# SensePlates.net
KiCad netlist of a schematic drawn in Altium Designer
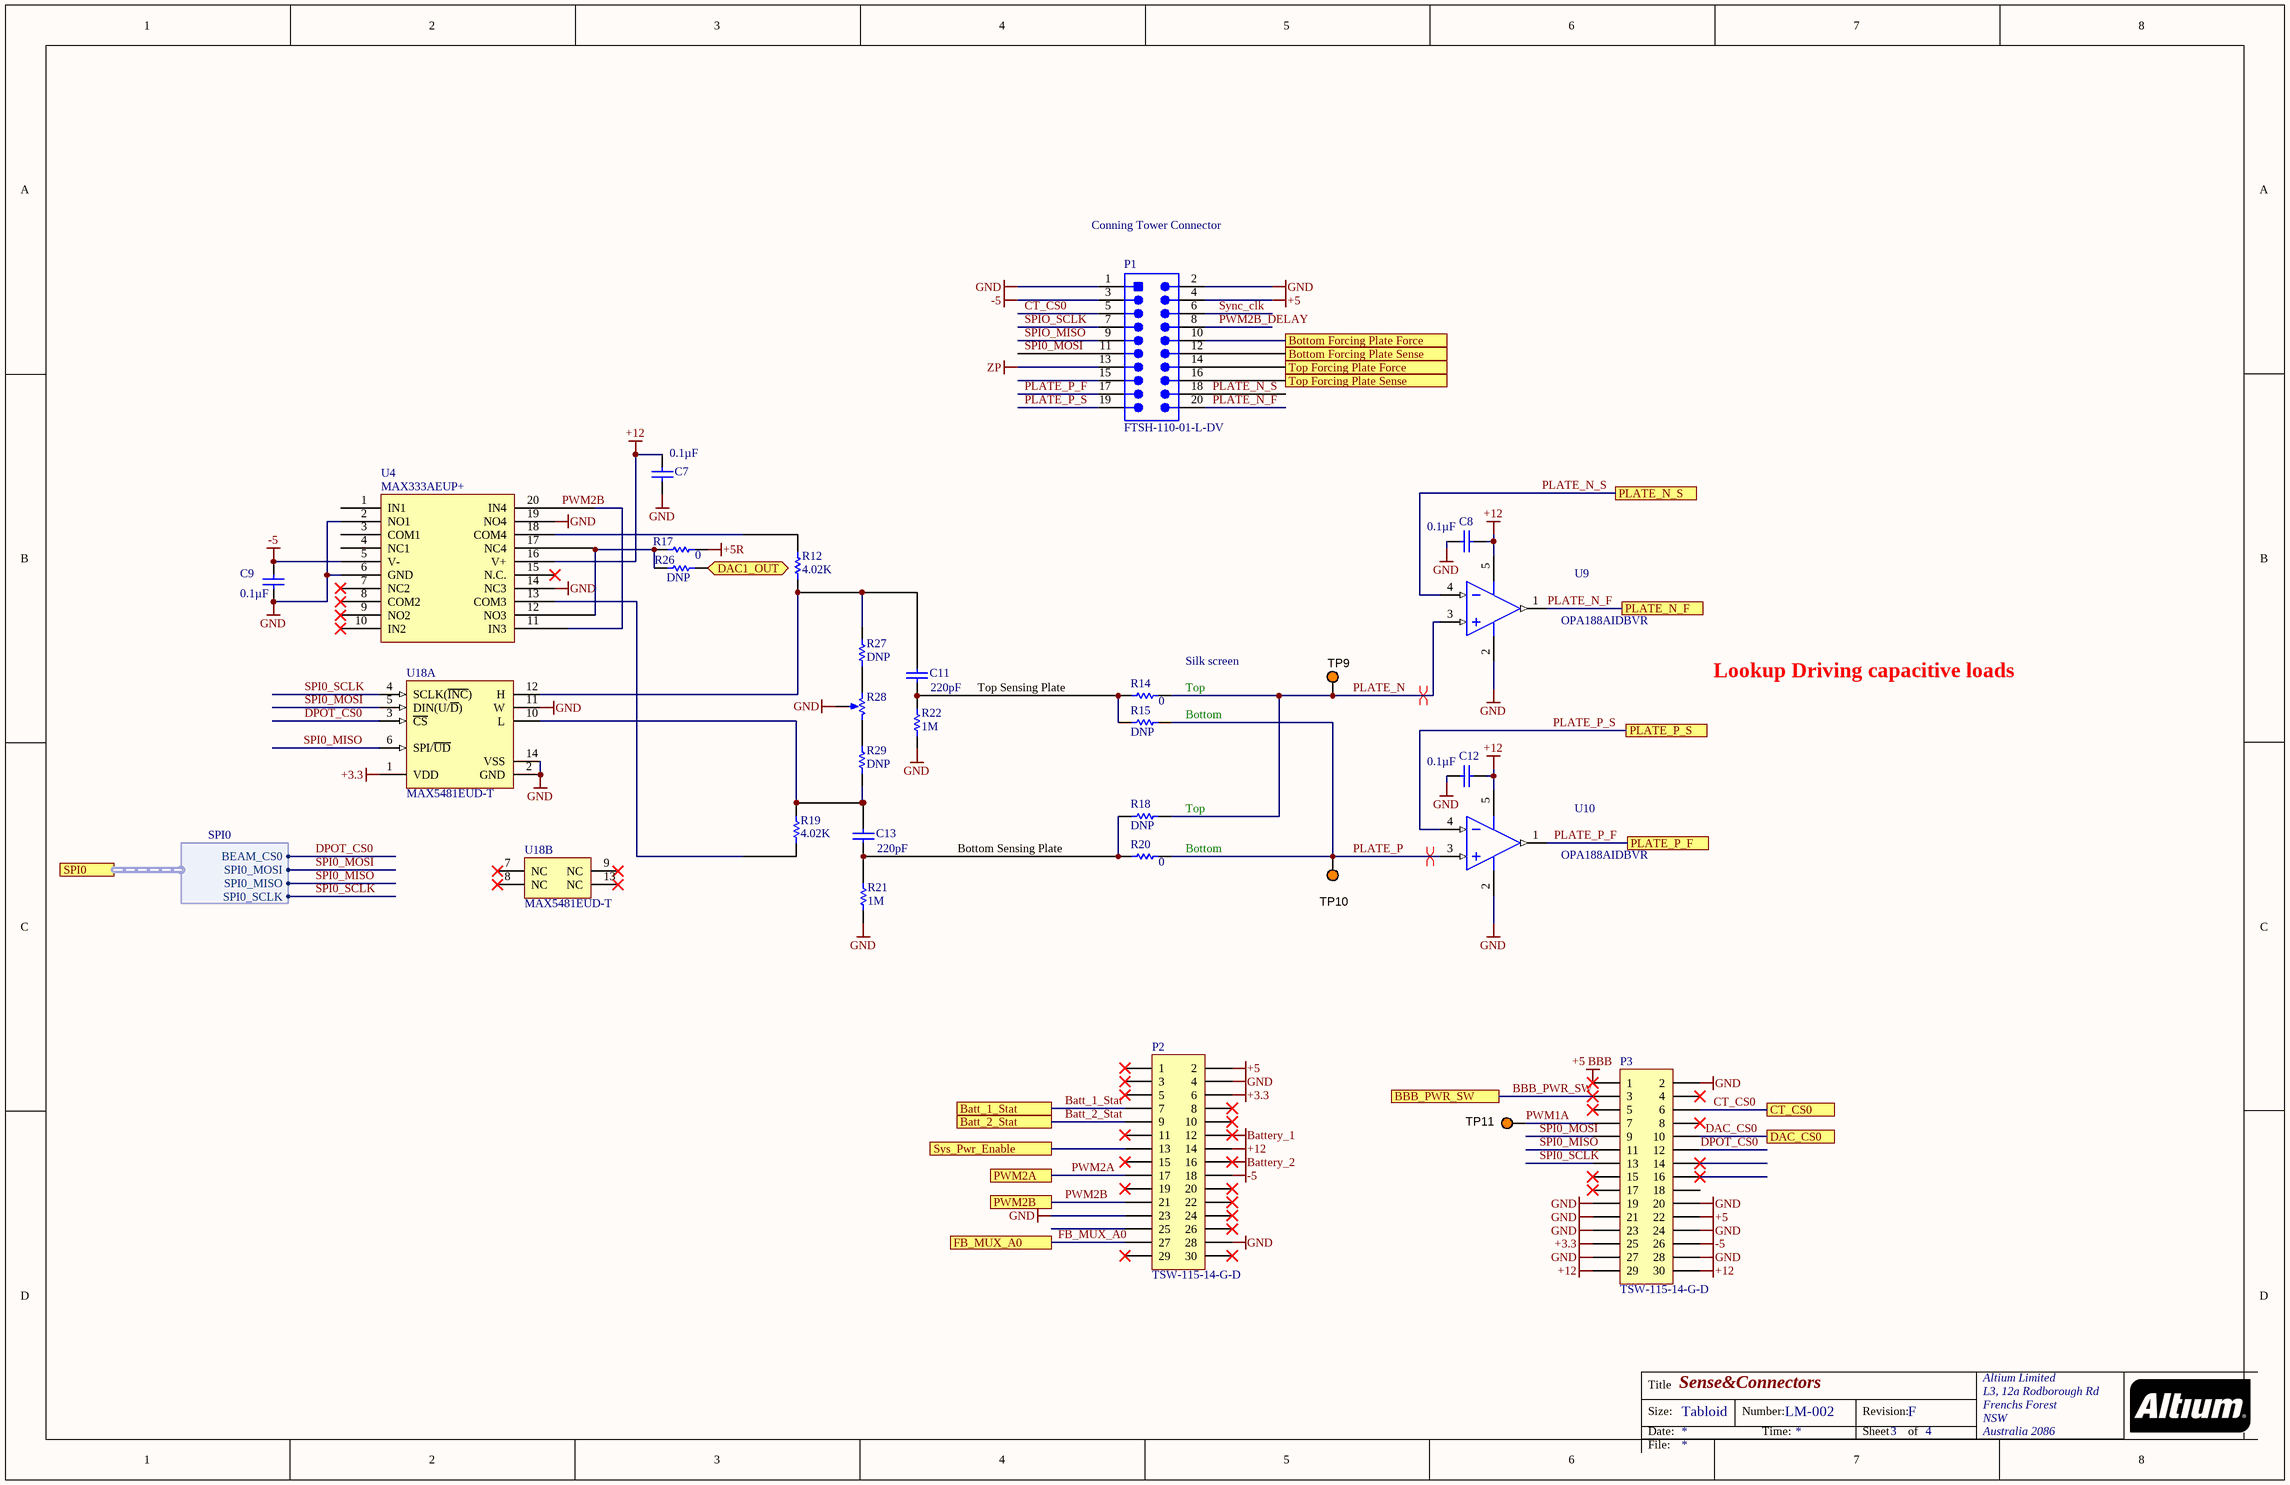
[diagram p0: SensePlates.SchDoc]

(export (version "E")
  (design (tool "Eeschema 10.0.6"))
  (components
    (comp (ref "C7")
      (value "CAP CER 0.1UF 25V X7R 0805")
      (footprint "CAPC0805(2012)145_N")
      (fields
        (field (name "MANUFACTURER") "Murata Electronics North America")
        (field (name "MANUFACTURER PART NUMBER") "GRM21BR71E104KA01L")
        (field (name "CAPACITANCE") "0.1µF")
        (field (name "TOLERANCE") "±10%")
      )
      (libsource (lib "Altium Content Vault") (part "CMP-1036-04795-1"))
    )
    (comp (ref "C8")
      (value "CAP CER 0.1UF 25V X7R 0805")
      (footprint "CAPC0805(2012)145_N")
      (fields
        (field (name "MANUFACTURER") "Murata Electronics North America")
        (field (name "MANUFACTURER PART NUMBER") "GRM21BR71E104KA01L")
        (field (name "CAPACITANCE") "0.1µF")
        (field (name "TOLERANCE") "±10%")
      )
      (libsource (lib "Altium Content Vault") (part "CMP-1036-04795-1"))
    )
    (comp (ref "C9")
      (value "CAP CER 0.1UF 25V X7R 0805")
      (footprint "CAPC0805(2012)145_N")
      (fields
        (field (name "MANUFACTURER") "Murata Electronics North America")
        (field (name "MANUFACTURER PART NUMBER") "GRM21BR71E104KA01L")
        (field (name "CAPACITANCE") "0.1µF")
        (field (name "TOLERANCE") "±10%")
      )
      (libsource (lib "Altium Content Vault") (part "CMP-1036-04795-1"))
    )
    (comp (ref "C11")
      (value "CAP CER 1UF 25V X7R 0805")
      (footprint "CAPC0805(2012)155_L")
      (fields
        (field (name "MANUFACTURER") "Murata Electronics North America")
        (field (name "MANUFACTURER PART NUMBER") "GRM21BR71E105KA99L")
        (field (name "CAPACITANCE") "220pF")
        (field (name "TOLERANCE") "±10%")
      )
      (libsource (lib "Altium Content Vault") (part "CMP-1036-04882-1"))
    )
    (comp (ref "C12")
      (value "CAP CER 0.1UF 25V X7R 0805")
      (footprint "CAPC0805(2012)145_N")
      (fields
        (field (name "MANUFACTURER") "Murata Electronics North America")
        (field (name "MANUFACTURER PART NUMBER") "GRM21BR71E104KA01L")
        (field (name "CAPACITANCE") "0.1µF")
        (field (name "TOLERANCE") "±10%")
      )
      (libsource (lib "Altium Content Vault") (part "CMP-1036-04795-1"))
    )
    (comp (ref "C13")
      (value "CAP CER 1UF 25V X7R 0805")
      (footprint "CAPC0805(2012)155_L")
      (fields
        (field (name "MANUFACTURER") "Murata Electronics North America")
        (field (name "MANUFACTURER PART NUMBER") "GRM21BR71E105KA99L")
        (field (name "CAPACITANCE") "220pF")
        (field (name "TOLERANCE") "±10%")
      )
      (libsource (lib "Altium Content Vault") (part "CMP-1036-04882-1"))
    )
    (comp (ref "P1")
      (value "FTSH-110-01-L-DV")
      (footprint "SMTC-FTSH-110-01-L-DV_V")
      (description "Male Header, Pitch 1.27 mm, 2 x 10 Position, Height 6.1 mm, -55 to 125 degC, RoHS, Tube")
      (fields (field (name "MANUFACTURER") "Samtec"))
      (libsource (lib "Altium Content Vault") (part "CN-2P-M-R20_V1"))
    )
    (comp (ref "P2")
      (value "TSW-115-14-G-D")
      (footprint "TSW-115-14-G-D")
      (description "Header, 15-Pin, Dual row")
      (fields (field (name "MANUFACTURER") "Samtec Inc."))
      (libsource (lib "Miscellaneous Connectors") (part "Header 15X2"))
    )
    (comp (ref "P3")
      (value "TSW-115-14-G-D")
      (footprint "TSW-115-14-G-D")
      (description "Header, 15-Pin, Dual row")
      (fields (field (name "MANUFACTURER") "Samtec Inc."))
      (libsource (lib "Miscellaneous Connectors") (part "Header 15X2"))
    )
    (comp (ref "R12")
      (value "4.02K")
      (footprint "RESC0805(2012)_L")
      (description "RES SMD 4.02K OHM 1% 1/8W 0805")
      (fields
        (field (name "MANUFACTURER") "Vishay Dale")
        (field (name "MANUFACTURER PART NUMBER") "CRCW08054K02FKEAHP")
      )
      (libsource (lib "Altium Content Vault") (part "CMP-1013-00215-1"))
    )
    (comp (ref "R14")
      (value "0")
      (footprint "RESC0805(2012)_L")
      (description "RES SMD 0 OHM JUMPER 1/8W 0805")
      (fields
        (field (name "MANUFACTURER") "Panasonic Electronic Components")
        (field (name "MANUFACTURER PART NUMBER") "ERJ-6GEY0R00V")
      )
      (libsource (lib "Altium Content Vault") (part "CMP-1013-00215-1"))
    )
    (comp (ref "R15")
      (value "DNP")
      (footprint "RESC0805(2012)_L")
      (description "RES SMD 0 OHM JUMPER 1/8W 0805")
      (fields
        (field (name "MANUFACTURER") "Panasonic Electronic Components")
        (field (name "MANUFACTURER PART NUMBER") "ERJ-6GEY0R00V")
      )
      (libsource (lib "Altium Content Vault") (part "CMP-1013-00215-1"))
    )
    (comp (ref "R17")
      (value "0")
      (footprint "RESC0805(2012)_L")
      (description "RES SMD 0 OHM JUMPER 1/8W 0805")
      (fields
        (field (name "MANUFACTURER") "Panasonic Electronic Components")
        (field (name "MANUFACTURER PART NUMBER") "ERJ-6GEY0R00V")
      )
      (libsource (lib "Altium Content Vault") (part "CMP-1013-00215-1"))
    )
    (comp (ref "R18")
      (value "DNP")
      (footprint "RESC0805(2012)_L")
      (description "RES SMD 0 OHM JUMPER 1/8W 0805")
      (fields
        (field (name "MANUFACTURER") "Panasonic Electronic Components")
        (field (name "MANUFACTURER PART NUMBER") "ERJ-6GEY0R00V")
      )
      (libsource (lib "Altium Content Vault") (part "CMP-1013-00215-1"))
    )
    (comp (ref "R19")
      (value "4.02K")
      (footprint "RESC0805(2012)_L")
      (description "RES SMD 4.02K OHM 1% 1/8W 0805")
      (fields
        (field (name "MANUFACTURER") "Vishay Dale")
        (field (name "MANUFACTURER PART NUMBER") "CRCW08054K02FKEAHP")
      )
      (libsource (lib "Altium Content Vault") (part "CMP-1013-00215-1"))
    )
    (comp (ref "R20")
      (value "0")
      (footprint "RESC0805(2012)_L")
      (description "RES SMD 0 OHM JUMPER 1/8W 0805")
      (fields
        (field (name "MANUFACTURER") "Panasonic Electronic Components")
        (field (name "MANUFACTURER PART NUMBER") "ERJ-6GEY0R00V")
      )
      (libsource (lib "Altium Content Vault") (part "CMP-1013-00215-1"))
    )
    (comp (ref "R21")
      (value "1M")
      (footprint "RESC0805(2012)_L")
      (description "RES SMD 1M OHM 1% 1/8W 0805")
      (fields
        (field (name "MANUFACTURER") "Vishay Dale")
        (field (name "MANUFACTURER PART NUMBER") "RCV08051M00FKEA")
      )
      (libsource (lib "Altium Content Vault") (part "CMP-1013-00215-1"))
    )
    (comp (ref "R22")
      (value "1M")
      (footprint "RESC0805(2012)_L")
      (description "RES SMD 1M OHM 1% 1/8W 0805")
      (fields
        (field (name "MANUFACTURER") "Vishay Dale")
        (field (name "MANUFACTURER PART NUMBER") "RCV08051M00FKEA")
      )
      (libsource (lib "Altium Content Vault") (part "CMP-1013-00215-1"))
    )
    (comp (ref "R26")
      (value "DNP")
      (footprint "RESC0805(2012)_L")
      (description "RES SMD 0 OHM JUMPER 1/8W 0805")
      (fields
        (field (name "MANUFACTURER") "Panasonic Electronic Components")
        (field (name "MANUFACTURER PART NUMBER") "ERJ-6GEY0R00V")
      )
      (libsource (lib "Altium Content Vault") (part "CMP-1013-00215-1"))
    )
    (comp (ref "R27")
      (value "DNP")
      (footprint "RESC0402(1005)_M")
      (description "7.5K")
      (libsource (lib "Altium Content Vault") (part "CMP-1011-00463-1"))
    )
    (comp (ref "R28")
      (value "DNP")
      (footprint "Trimmer 2.54")
      (description "TRIMMER 5K OHM 0.25W PC PIN")
      (fields
        (field (name "MANUFACTURER") "Vishay Foil Resistors (Division of Vishay Precision Group)")
        (field (name "MANUFACTURER PART NUMBER") "Y00535K00000J0L")
      )
      (libsource (lib "ZLS_Schematic_lib") (part "Trimmer"))
    )
    (comp (ref "R29")
      (value "DNP")
      (footprint "RESC0402(1005)_M")
      (description "7.5K")
      (libsource (lib "Altium Content Vault") (part "CMP-1011-00463-1"))
    )
    (comp (ref "TP9")
      (value "5003")
      (footprint "KSTN-5003")
      (description "Test Point, Orange, 1-Pin THD, RoHS")
      (libsource (lib "Altium Content Vault") (part "CMP-1672-00009-1"))
    )
    (comp (ref "TP10")
      (value "5003")
      (footprint "KSTN-5003")
      (description "Test Point, Orange, 1-Pin THD, RoHS")
      (libsource (lib "Altium Content Vault") (part "CMP-1672-00009-1"))
    )
    (comp (ref "TP11")
      (value "5003")
      (footprint "KSTN-5003")
      (description "Test Point, Orange, 1-Pin THD, RoHS")
      (libsource (lib "Altium Content Vault") (part "CMP-1672-00009-1"))
    )
    (comp (ref "U4")
      (value "MAX333AEUP+")
      (footprint "TSOP65P640X90-20N")
      (description "IC SWITCH QUAD SPDT 20TSSOP")
      (fields (field (name "MANUFACTURER") "Maxim Integrated") (field (name "BASE PART NUMBER") "MAX333"))
      (libsource (lib "ZLS_Schematic_lib") (part "MAX333CWP+"))
    )
    (comp (ref "U9")
      (value "OPA188AIDBVR")
      (footprint "DBV0005A_M")
      (fields (field (name "MANUFACTURER") "Texas Instruments"))
      (libsource (lib "Altium Content Vault") (part "CMP-0809-00005-2"))
    )
    (comp (ref "U10")
      (value "OPA188AIDBVR")
      (footprint "DBV0005A_M")
      (fields (field (name "MANUFACTURER") "Texas Instruments"))
      (libsource (lib "Altium Content Vault") (part "CMP-0809-00005-2"))
    )
    (comp (ref "U18")
      (value "MAX5481EUD-T")
      (footprint "MAXM-U14-1_M")
      (libsource (lib "Altium Content Vault") (part "MAX548X-U14"))
    )
  )
  (nets
    (net (code "2") (name "+3.3") (class "Default")
      (node (ref "P2") (pin "6") (pinfunction "6_6") (pintype "passive"))
      (node (ref "P3") (pin "25") (pinfunction "25_25") (pintype "passive"))
      (node (ref "U18") (pin "1") (pinfunction "VDD_1") (pintype "power_in"))
    )
    (net (code "3") (name "+5") (class "Default")
      (node (ref "P1") (pin "4") (pinfunction "4_4") (pintype "passive"))
      (node (ref "P2") (pin "2") (pinfunction "2_2") (pintype "passive"))
      (node (ref "P3") (pin "22") (pinfunction "22_22") (pintype "passive"))
    )
    (net (code "4") (name "+5 BBB") (class "Default")
      (node (ref "P3") (pin "1") (pinfunction "1_1") (pintype "passive"))
    )
    (net (code "5") (name "+5R") (class "Default")
      (node (ref "R17") (pin "1") (pinfunction "1_1") (pintype "passive"))
    )
    (net (code "6") (name "+12") (class "Default")
      (node (ref "C12") (pin "2") (pinfunction "2_2") (pintype "passive"))
      (node (ref "C7") (pin "1") (pinfunction "1_1") (pintype "passive"))
      (node (ref "C8") (pin "2") (pinfunction "2_2") (pintype "passive"))
      (node (ref "P2") (pin "14") (pinfunction "14_14") (pintype "passive"))
      (node (ref "P3") (pin "29") (pinfunction "29_29") (pintype "passive"))
      (node (ref "P3") (pin "30") (pinfunction "30_30") (pintype "passive"))
      (node (ref "U10") (pin "5") (pinfunction "V+_5") (pintype "power_in"))
      (node (ref "U4") (pin "16") (pinfunction "V+_16") (pintype "power_in"))
      (node (ref "U9") (pin "5") (pinfunction "V+_5") (pintype "power_in"))
    )
    (net (code "7") (name "-5") (class "Default")
      (node (ref "C9") (pin "1") (pinfunction "1_1") (pintype "passive"))
      (node (ref "P1") (pin "3") (pinfunction "3_3") (pintype "passive"))
      (node (ref "P2") (pin "18") (pinfunction "18_18") (pintype "passive"))
      (node (ref "P3") (pin "26") (pinfunction "26_26") (pintype "passive"))
      (node (ref "U4") (pin "5") (pinfunction "V-_5") (pintype "power_in"))
    )
    (net (code "8") (name "/BBB_PWR_SW") (class "Default")
      (node (ref "P3") (pin "3") (pinfunction "3_3") (pintype "passive+no_connect"))
    )
    (net (code "9") (name "/Batt_1_Stat") (class "Default")
      (node (ref "P2") (pin "7") (pinfunction "7_7") (pintype "passive"))
    )
    (net (code "10") (name "/Batt_2_Stat") (class "Default")
      (node (ref "P2") (pin "9") (pinfunction "9_9") (pintype "passive"))
    )
    (net (code "11") (name "/Bottom Forcing Plate Force") (class "Default")
      (node (ref "P1") (pin "10") (pinfunction "10_10") (pintype "passive"))
    )
    (net (code "12") (name "/Bottom Forcing Plate Sense") (class "Default")
      (node (ref "P1") (pin "12") (pinfunction "12_12") (pintype "passive"))
    )
    (net (code "13") (name "/CT_CS0") (class "Default")
      (node (ref "P1") (pin "5") (pinfunction "5_5") (pintype "passive"))
      (node (ref "P3") (pin "6") (pinfunction "6_6") (pintype "passive"))
    )
    (net (code "14") (name "/DAC1_OUT") (class "Default")
      (node (ref "R26") (pin "1") (pinfunction "1_1") (pintype "passive"))
    )
    (net (code "15") (name "/DAC_CS0") (class "Default")
      (node (ref "P3") (pin "10") (pinfunction "10_10") (pintype "passive"))
    )
    (net (code "16") (name "/DPOT_CS0") (class "Default")
      (node (ref "P3") (pin "12") (pinfunction "12_12") (pintype "passive"))
      (node (ref "U18") (pin "3") (pinfunction "~{CS}_3") (pintype "input"))
    )
    (net (code "17") (name "/FB_MUX_A0") (class "Default")
      (node (ref "P2") (pin "27") (pinfunction "27_27") (pintype "passive"))
    )
    (net (code "18") (name "/PLATE_N") (class "Default")
      (node (ref "R14") (pin "1") (pinfunction "1_1") (pintype "passive"))
      (node (ref "R18") (pin "1") (pinfunction "1_1") (pintype "passive"))
      (node (ref "TP9") (pin "1") (pinfunction "1_1") (pintype "passive"))
      (node (ref "U9") (pin "3") (pinfunction "IN+_3") (pintype "input"))
    )
    (net (code "19") (name "/PLATE_N_F") (class "Default")
      (node (ref "P1") (pin "20") (pinfunction "20_20") (pintype "passive"))
      (node (ref "U9") (pin "1") (pinfunction "OUT_1") (pintype "output"))
    )
    (net (code "20") (name "/PLATE_N_S") (class "Default")
      (node (ref "P1") (pin "18") (pinfunction "18_18") (pintype "passive"))
      (node (ref "U9") (pin "4") (pinfunction "IN-_4") (pintype "input"))
    )
    (net (code "21") (name "/PLATE_P") (class "Default")
      (node (ref "R15") (pin "1") (pinfunction "1_1") (pintype "passive"))
      (node (ref "R20") (pin "1") (pinfunction "1_1") (pintype "passive"))
      (node (ref "TP10") (pin "1") (pinfunction "1_1") (pintype "passive"))
      (node (ref "U10") (pin "3") (pinfunction "IN+_3") (pintype "input"))
    )
    (net (code "22") (name "/PLATE_P_F") (class "Default")
      (node (ref "P1") (pin "17") (pinfunction "17_17") (pintype "passive"))
      (node (ref "U10") (pin "1") (pinfunction "OUT_1") (pintype "output"))
    )
    (net (code "23") (name "/PLATE_P_S") (class "Default")
      (node (ref "P1") (pin "19") (pinfunction "19_19") (pintype "passive"))
      (node (ref "U10") (pin "4") (pinfunction "IN-_4") (pintype "input"))
    )
    (net (code "24") (name "/PWM1A") (class "Default")
      (node (ref "P3") (pin "7") (pinfunction "7_7") (pintype "passive"))
      (node (ref "TP11") (pin "1") (pinfunction "1_1") (pintype "passive"))
    )
    (net (code "25") (name "/PWM2A") (class "Default")
      (node (ref "P2") (pin "17") (pinfunction "17_17") (pintype "passive"))
    )
    (net (code "26") (name "/PWM2B") (class "Default")
      (node (ref "P2") (pin "21") (pinfunction "21_21") (pintype "passive"))
      (node (ref "U4") (pin "11") (pinfunction "IN3_11") (pintype "passive"))
      (node (ref "U4") (pin "20") (pinfunction "IN4_20") (pintype "passive"))
    )
    (net (code "27") (name "/PWM2B_DELAY") (class "Default")
      (node (ref "P1") (pin "8") (pinfunction "8_8") (pintype "passive"))
    )
    (net (code "28") (name "/SPI0_MISO") (class "Default")
      (node (ref "P3") (pin "11") (pinfunction "11_11") (pintype "passive"))
      (node (ref "U18") (pin "6") (pinfunction "SPI/~{UD}_6") (pintype "input"))
    )
    (net (code "29") (name "/SPI0_MOSI") (class "Default")
      (node (ref "P1") (pin "11") (pinfunction "11_11") (pintype "passive"))
      (node (ref "P3") (pin "9") (pinfunction "9_9") (pintype "passive"))
      (node (ref "U18") (pin "5") (pinfunction "DIN(U/~{D})_5") (pintype "input"))
    )
    (net (code "30") (name "/SPI0_SCLK") (class "Default")
      (node (ref "P3") (pin "13") (pinfunction "13_13") (pintype "passive"))
      (node (ref "U18") (pin "4") (pinfunction "SCLK(~{INC})_4") (pintype "input"))
    )
    (net (code "31") (name "/SPIO_MISO") (class "Default")
      (node (ref "P1") (pin "9") (pinfunction "9_9") (pintype "passive"))
    )
    (net (code "32") (name "/SPIO_SCLK") (class "Default")
      (node (ref "P1") (pin "7") (pinfunction "7_7") (pintype "passive"))
    )
    (net (code "33") (name "/Sync_clk") (class "Default")
      (node (ref "P1") (pin "6") (pinfunction "6_6") (pintype "passive"))
    )
    (net (code "34") (name "/Sys_Pwr_Enable") (class "Default")
      (node (ref "P2") (pin "13") (pinfunction "13_13") (pintype "passive"))
    )
    (net (code "35") (name "/Top Forcing Plate Force") (class "Default")
      (node (ref "P1") (pin "14") (pinfunction "14_14") (pintype "passive"))
    )
    (net (code "36") (name "/Top Forcing Plate Sense") (class "Default")
      (node (ref "P1") (pin "16") (pinfunction "16_16") (pintype "passive"))
    )
    (net (code "38") (name "Battery_1") (class "Default")
      (node (ref "P2") (pin "12") (pinfunction "12_12") (pintype "passive"))
    )
    (net (code "39") (name "Battery_2") (class "Default")
      (node (ref "P2") (pin "16") (pinfunction "16_16") (pintype "passive"))
    )
    (net (code "40") (name "GND") (class "Default")
      (node (ref "C12") (pin "1") (pinfunction "1_1") (pintype "passive"))
      (node (ref "C7") (pin "2") (pinfunction "2_2") (pintype "passive"))
      (node (ref "C8") (pin "1") (pinfunction "1_1") (pintype "passive"))
      (node (ref "C9") (pin "2") (pinfunction "2_2") (pintype "passive"))
      (node (ref "P1") (pin "1") (pinfunction "1_1") (pintype "passive"))
      (node (ref "P1") (pin "2") (pinfunction "2_2") (pintype "passive"))
      (node (ref "P2") (pin "23") (pinfunction "23_23") (pintype "passive"))
      (node (ref "P2") (pin "28") (pinfunction "28_28") (pintype "passive"))
      (node (ref "P2") (pin "4") (pinfunction "4_4") (pintype "passive"))
      (node (ref "P3") (pin "19") (pinfunction "19_19") (pintype "passive"))
      (node (ref "P3") (pin "2") (pinfunction "2_2") (pintype "passive"))
      (node (ref "P3") (pin "20") (pinfunction "20_20") (pintype "passive"))
      (node (ref "P3") (pin "21") (pinfunction "21_21") (pintype "passive"))
      (node (ref "P3") (pin "23") (pinfunction "23_23") (pintype "passive"))
      (node (ref "P3") (pin "24") (pinfunction "24_24") (pintype "passive"))
      (node (ref "P3") (pin "27") (pinfunction "27_27") (pintype "passive"))
      (node (ref "P3") (pin "28") (pinfunction "28_28") (pintype "passive"))
      (node (ref "R21") (pin "1") (pinfunction "1_1") (pintype "passive"))
      (node (ref "R22") (pin "1") (pinfunction "1_1") (pintype "passive"))
      (node (ref "R28") (pin "2") (pinfunction "b_2") (pintype "passive"))
      (node (ref "U10") (pin "2") (pinfunction "V-_2") (pintype "power_in"))
      (node (ref "U18") (pin "11") (pinfunction "W_11") (pintype "passive"))
      (node (ref "U18") (pin "14") (pinfunction "VSS_14") (pintype "power_in"))
      (node (ref "U18") (pin "2") (pinfunction "GND_2") (pintype "power_in"))
      (node (ref "U4") (pin "14") (pinfunction "NC3_14") (pintype "passive"))
      (node (ref "U4") (pin "19") (pinfunction "NO4_19") (pintype "passive"))
      (node (ref "U4") (pin "2") (pinfunction "NO1_2") (pintype "passive"))
      (node (ref "U4") (pin "6") (pinfunction "GND_6") (pintype "passive"))
      (node (ref "U9") (pin "2") (pinfunction "V-_2") (pintype "power_in"))
    )
    (net (code "41") (name "Net-(C11-Pad1)") (class "Default")
      (node (ref "C11") (pin "1") (pinfunction "1_1") (pintype "passive"))
      (node (ref "R14") (pin "2") (pinfunction "2_2") (pintype "passive"))
      (node (ref "R15") (pin "2") (pinfunction "2_2") (pintype "passive"))
      (node (ref "R22") (pin "2") (pinfunction "2_2") (pintype "passive"))
    )
    (net (code "42") (name "Net-(C13-Pad1)") (class "Default")
      (node (ref "C13") (pin "1") (pinfunction "1_1") (pintype "passive"))
      (node (ref "R18") (pin "2") (pinfunction "2_2") (pintype "passive"))
      (node (ref "R20") (pin "2") (pinfunction "2_2") (pintype "passive"))
      (node (ref "R21") (pin "2") (pinfunction "2_2") (pintype "passive"))
    )
    (net (code "43") (name "Net-(R28-a)") (class "Default")
      (node (ref "R27") (pin "1") (pinfunction "1_1") (pintype "passive"))
      (node (ref "R28") (pin "1") (pinfunction "a_1") (pintype "passive"))
    )
    (net (code "44") (name "Net-(R28-c)") (class "Default")
      (node (ref "R28") (pin "3") (pinfunction "c_3") (pintype "passive"))
      (node (ref "R29") (pin "2") (pinfunction "2_2") (pintype "passive"))
    )
    (net (code "45") (name "Net-(U4-COM3)") (class "Default")
      (node (ref "R19") (pin "1") (pinfunction "1_1") (pintype "passive"))
      (node (ref "U4") (pin "13") (pinfunction "COM3_13") (pintype "passive"))
    )
    (net (code "46") (name "Net-(U4-COM4)") (class "Default")
      (node (ref "R12") (pin "2") (pinfunction "2_2") (pintype "passive"))
      (node (ref "U4") (pin "18") (pinfunction "COM4_18") (pintype "passive"))
    )
    (net (code "47") (name "Net-(U4-NC4)") (class "Default")
      (node (ref "R17") (pin "2") (pinfunction "2_2") (pintype "passive"))
      (node (ref "R26") (pin "2") (pinfunction "2_2") (pintype "passive"))
      (node (ref "U4") (pin "12") (pinfunction "NO3_12") (pintype "passive"))
      (node (ref "U4") (pin "17") (pinfunction "NC4_17") (pintype "passive"))
    )
    (net (code "48") (name "Net-(U18A-H)") (class "Default")
      (node (ref "C11") (pin "2") (pinfunction "2_2") (pintype "passive"))
      (node (ref "R12") (pin "1") (pinfunction "1_1") (pintype "passive"))
      (node (ref "R27") (pin "2") (pinfunction "2_2") (pintype "passive"))
      (node (ref "U18") (pin "12") (pinfunction "H_12") (pintype "passive"))
    )
    (net (code "49") (name "Net-(U18A-L)") (class "Default")
      (node (ref "C13") (pin "2") (pinfunction "2_2") (pintype "passive"))
      (node (ref "R19") (pin "2") (pinfunction "2_2") (pintype "passive"))
      (node (ref "R29") (pin "1") (pinfunction "1_1") (pintype "passive"))
      (node (ref "U18") (pin "10") (pinfunction "L_10") (pintype "passive"))
    )
    (net (code "50") (name "ZP") (class "Default")
      (node (ref "P1") (pin "13") (pinfunction "13_13") (pintype "passive"))
    )
    (net (code "51") (name "unconnected-(P1-Pad15)") (class "Default")
      (node (ref "P1") (pin "15") (pinfunction "15_15") (pintype "passive"))
    )
    (net (code "52") (name "unconnected-(P2-Pad1)") (class "Default")
      (node (ref "P2") (pin "1") (pinfunction "1_1") (pintype "passive+no_connect"))
    )
    (net (code "53") (name "unconnected-(P2-Pad3)") (class "Default")
      (node (ref "P2") (pin "3") (pinfunction "3_3") (pintype "passive+no_connect"))
    )
    (net (code "54") (name "unconnected-(P2-Pad5)") (class "Default")
      (node (ref "P2") (pin "5") (pinfunction "5_5") (pintype "passive+no_connect"))
    )
    (net (code "55") (name "unconnected-(P2-Pad8)") (class "Default")
      (node (ref "P2") (pin "8") (pinfunction "8_8") (pintype "passive+no_connect"))
    )
    (net (code "56") (name "unconnected-(P2-Pad10)") (class "Default")
      (node (ref "P2") (pin "10") (pinfunction "10_10") (pintype "passive+no_connect"))
    )
    (net (code "57") (name "unconnected-(P2-Pad11)") (class "Default")
      (node (ref "P2") (pin "11") (pinfunction "11_11") (pintype "passive+no_connect"))
    )
    (net (code "58") (name "unconnected-(P2-Pad15)") (class "Default")
      (node (ref "P2") (pin "15") (pinfunction "15_15") (pintype "passive+no_connect"))
    )
    (net (code "59") (name "unconnected-(P2-Pad19)") (class "Default")
      (node (ref "P2") (pin "19") (pinfunction "19_19") (pintype "passive+no_connect"))
    )
    (net (code "60") (name "unconnected-(P2-Pad20)") (class "Default")
      (node (ref "P2") (pin "20") (pinfunction "20_20") (pintype "passive+no_connect"))
    )
    (net (code "61") (name "unconnected-(P2-Pad22)") (class "Default")
      (node (ref "P2") (pin "22") (pinfunction "22_22") (pintype "passive+no_connect"))
    )
    (net (code "62") (name "unconnected-(P2-Pad24)") (class "Default")
      (node (ref "P2") (pin "24") (pinfunction "24_24") (pintype "passive+no_connect"))
    )
    (net (code "63") (name "unconnected-(P2-Pad25)") (class "Default")
      (node (ref "P2") (pin "25") (pinfunction "25_25") (pintype "passive"))
    )
    (net (code "64") (name "unconnected-(P2-Pad26)") (class "Default")
      (node (ref "P2") (pin "26") (pinfunction "26_26") (pintype "passive+no_connect"))
    )
    (net (code "65") (name "unconnected-(P2-Pad29)") (class "Default")
      (node (ref "P2") (pin "29") (pinfunction "29_29") (pintype "passive+no_connect"))
    )
    (net (code "66") (name "unconnected-(P2-Pad30)") (class "Default")
      (node (ref "P2") (pin "30") (pinfunction "30_30") (pintype "passive+no_connect"))
    )
    (net (code "67") (name "unconnected-(P3-Pad4)") (class "Default")
      (node (ref "P3") (pin "4") (pinfunction "4_4") (pintype "passive+no_connect"))
    )
    (net (code "68") (name "unconnected-(P3-Pad5)") (class "Default")
      (node (ref "P3") (pin "5") (pinfunction "5_5") (pintype "passive+no_connect"))
    )
    (net (code "69") (name "unconnected-(P3-Pad8)") (class "Default")
      (node (ref "P3") (pin "8") (pinfunction "8_8") (pintype "passive+no_connect"))
    )
    (net (code "70") (name "unconnected-(P3-Pad14)") (class "Default")
      (node (ref "P3") (pin "14") (pinfunction "14_14") (pintype "passive+no_connect"))
    )
    (net (code "71") (name "unconnected-(P3-Pad15)") (class "Default")
      (node (ref "P3") (pin "15") (pinfunction "15_15") (pintype "passive+no_connect"))
    )
    (net (code "72") (name "unconnected-(P3-Pad16)") (class "Default")
      (node (ref "P3") (pin "16") (pinfunction "16_16") (pintype "passive+no_connect"))
    )
    (net (code "73") (name "unconnected-(P3-Pad17)") (class "Default")
      (node (ref "P3") (pin "17") (pinfunction "17_17") (pintype "passive+no_connect"))
    )
    (net (code "74") (name "unconnected-(P3-Pad18)") (class "Default")
      (node (ref "P3") (pin "18") (pinfunction "18_18") (pintype "passive"))
    )
    (net (code "75") (name "unconnected-(U4-COM1-Pad3)") (class "Default")
      (node (ref "U4") (pin "3") (pinfunction "COM1_3") (pintype "passive"))
    )
    (net (code "76") (name "unconnected-(U4-COM2-Pad8)") (class "Default")
      (node (ref "U4") (pin "8") (pinfunction "COM2_8") (pintype "passive+no_connect"))
    )
    (net (code "77") (name "unconnected-(U4-IN1-Pad1)") (class "Default")
      (node (ref "U4") (pin "1") (pinfunction "IN1_1") (pintype "passive"))
    )
    (net (code "78") (name "unconnected-(U4-IN2-Pad10)") (class "Default")
      (node (ref "U4") (pin "10") (pinfunction "IN2_10") (pintype "passive+no_connect"))
    )
    (net (code "79") (name "unconnected-(U4-N.C.-Pad15)") (class "Default")
      (node (ref "U4") (pin "15") (pinfunction "N.C._15") (pintype "passive+no_connect"))
    )
    (net (code "80") (name "unconnected-(U4-NC1-Pad4)") (class "Default")
      (node (ref "U4") (pin "4") (pinfunction "NC1_4") (pintype "passive"))
    )
    (net (code "81") (name "unconnected-(U4-NC2-Pad7)") (class "Default")
      (node (ref "U4") (pin "7") (pinfunction "NC2_7") (pintype "passive+no_connect"))
    )
    (net (code "82") (name "unconnected-(U4-NO2-Pad9)") (class "Default")
      (node (ref "U4") (pin "9") (pinfunction "NO2_9") (pintype "passive+no_connect"))
    )
    (net (code "83") (name "unconnected-(U18B-NC-Pad7)") (class "Default")
      (node (ref "U18") (pin "7") (pinfunction "NC_7") (pintype "passive+no_connect"))
    )
    (net (code "84") (name "unconnected-(U18B-NC-Pad8)") (class "Default")
      (node (ref "U18") (pin "8") (pinfunction "NC_8") (pintype "passive+no_connect"))
    )
    (net (code "85") (name "unconnected-(U18B-NC-Pad9)") (class "Default")
      (node (ref "U18") (pin "9") (pinfunction "NC_9") (pintype "passive+no_connect"))
    )
    (net (code "86") (name "unconnected-(U18B-NC-Pad13)") (class "Default")
      (node (ref "U18") (pin "13") (pinfunction "NC_13") (pintype "passive+no_connect"))
    )
  )
)
